# bridge.net
KiCad netlist of a schematic drawn in EAGLE
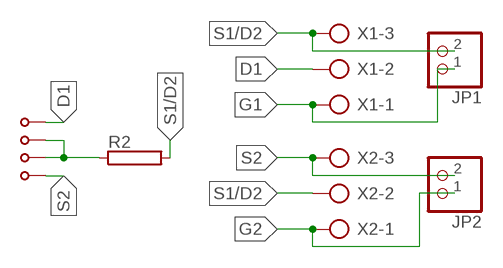
[diagram p0: schematic, sheet 1]

(export (version "E")
  (design (tool "Eeschema 10.0.6"))
  (components
    (comp (ref "JP1")
      (value "PINHD-1X2")
      (footprint "eagle-import:1X02")
      (libsource (lib "eagle-import") (part "PINHD-1X2"))
    )
    (comp (ref "JP2")
      (value "PINHD-1X2")
      (footprint "eagle-import:1X02")
      (libsource (lib "eagle-import") (part "PINHD-1X2"))
    )
    (comp (ref "R2")
      (value "RKH216-8")
      (footprint "eagle-import:KH216-8")
      (libsource (lib "eagle-import") (part "RKH216-8"))
    )
    (comp (ref "U$1")
      (value "BANANA-JACK")
      (footprint "eagle-import:BANANA-PRINT")
      (libsource (lib "eagle-import") (part "BANANA-JACK"))
    )
    (comp (ref "U$2")
      (value "BANANA-JACK")
      (footprint "eagle-import:BANANA-PRINT")
      (libsource (lib "eagle-import") (part "BANANA-JACK"))
    )
    (comp (ref "U$3")
      (value "BANANA-JACK")
      (footprint "eagle-import:BANANA-PRINT")
      (libsource (lib "eagle-import") (part "BANANA-JACK"))
    )
    (comp (ref "U$4")
      (value "BANANA-JACK")
      (footprint "eagle-import:BANANA-PRINT")
      (libsource (lib "eagle-import") (part "BANANA-JACK"))
    )
    (comp (ref "X1")
      (value "AK300/3")
      (footprint "eagle-import:AK300_3")
      (libsource (lib "eagle-import") (part "AK300/3"))
    )
    (comp (ref "X2")
      (value "AK300/3")
      (footprint "eagle-import:AK300_3")
      (libsource (lib "eagle-import") (part "AK300/3"))
    )
  )
  (nets
    (net (code "1") (name "D1") (class "Default")
      (node (ref "U$1") (pin "P$1") (pinfunction "PIN_P$1") (pintype "bidirectional"))
      (node (ref "X1") (pin "2") (pinfunction "KL_2") (pintype "passive"))
    )
    (net (code "2") (name "G1") (class "Default")
      (node (ref "JP1") (pin "1") (pinfunction "1_1") (pintype "passive"))
      (node (ref "X1") (pin "1") (pinfunction "KL_1") (pintype "passive"))
    )
    (net (code "3") (name "G2") (class "Default")
      (node (ref "JP2") (pin "1") (pinfunction "1_1") (pintype "passive"))
      (node (ref "X2") (pin "1") (pinfunction "KL_1") (pintype "passive"))
    )
    (net (code "4") (name "Net-(U$2-PIN)") (class "Default")
      (node (ref "R2") (pin "1") (pinfunction "1_1") (pintype "passive"))
      (node (ref "U$2") (pin "P$1") (pinfunction "PIN_P$1") (pintype "bidirectional"))
      (node (ref "U$3") (pin "P$1") (pinfunction "PIN_P$1") (pintype "bidirectional"))
    )
    (net (code "5") (name "S1{slash}D2") (class "Default")
      (node (ref "JP1") (pin "2") (pinfunction "2_2") (pintype "passive"))
      (node (ref "R2") (pin "2") (pinfunction "2_2") (pintype "passive"))
      (node (ref "X1") (pin "3") (pinfunction "KL_3") (pintype "passive"))
      (node (ref "X2") (pin "2") (pinfunction "KL_2") (pintype "passive"))
    )
    (net (code "6") (name "S2") (class "Default")
      (node (ref "JP2") (pin "2") (pinfunction "2_2") (pintype "passive"))
      (node (ref "U$4") (pin "P$1") (pinfunction "PIN_P$1") (pintype "bidirectional"))
      (node (ref "X2") (pin "3") (pinfunction "KL_3") (pintype "passive"))
    )
  )
)
